# 16_-ETH_SWITCH.net
KiCad netlist of a schematic drawn in Altium Designer
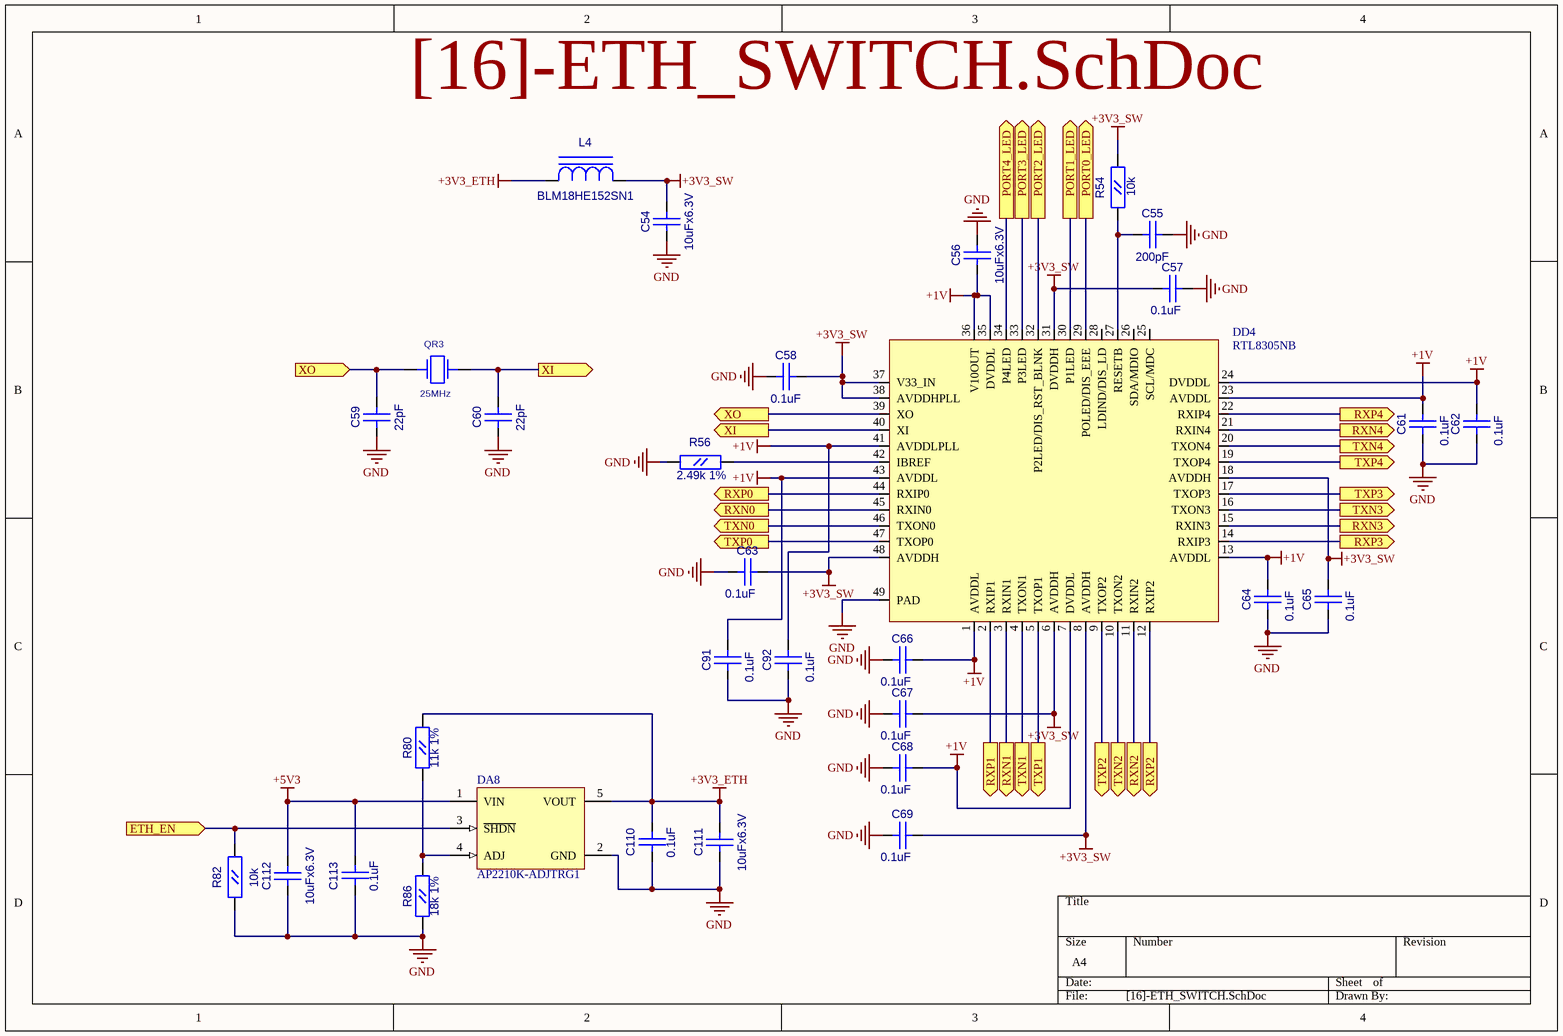
[diagram p0: [16]-ETH_SWITCH.SchDoc]

(export (version "E")
  (design (tool "Eeschema 10.0.6"))
  (components
    (comp (ref "C54")
      (value "10uFx6.3V")
      (footprint "CC0805")
      (description "CC0805")
      (libsource (lib "fizik_lib") (part "CC0805"))
    )
    (comp (ref "C55")
      (value "200pF")
      (footprint "CC0603")
      (description "CC0603")
      (libsource (lib "fizik_lib") (part "CC0603"))
    )
    (comp (ref "C56")
      (value "10uFx6.3V")
      (footprint "CC0805")
      (description "CC0805")
      (libsource (lib "fizik_lib") (part "CC0805"))
    )
    (comp (ref "C57")
      (value "0.1uF")
      (footprint "CC0603")
      (description "CC0603")
      (libsource (lib "fizik_lib") (part "CC0603"))
    )
    (comp (ref "C58")
      (value "0.1uF")
      (footprint "CC0603")
      (description "CC0603")
      (libsource (lib "fizik_lib") (part "CC0603"))
    )
    (comp (ref "C59")
      (value "22pF")
      (footprint "CC0603")
      (description "CC0603")
      (libsource (lib "fizik_lib") (part "CC0603"))
    )
    (comp (ref "C60")
      (value "22pF")
      (footprint "CC0603")
      (description "CC0603")
      (libsource (lib "fizik_lib") (part "CC0603"))
    )
    (comp (ref "C61")
      (value "0.1uF")
      (footprint "CC0603")
      (description "CC0603")
      (libsource (lib "fizik_lib") (part "CC0603"))
    )
    (comp (ref "C62")
      (value "0.1uF")
      (footprint "CC0603")
      (description "CC0603")
      (libsource (lib "fizik_lib") (part "CC0603"))
    )
    (comp (ref "C63")
      (value "0.1uF")
      (footprint "CC0603")
      (description "CC0603")
      (libsource (lib "fizik_lib") (part "CC0603"))
    )
    (comp (ref "C64")
      (value "0.1uF")
      (footprint "CC0603")
      (description "CC0603")
      (libsource (lib "fizik_lib") (part "CC0603"))
    )
    (comp (ref "C65")
      (value "0.1uF")
      (footprint "CC0603")
      (description "CC0603")
      (libsource (lib "fizik_lib") (part "CC0603"))
    )
    (comp (ref "C66")
      (value "0.1uF")
      (footprint "CC0603")
      (description "CC0603")
      (libsource (lib "fizik_lib") (part "CC0603"))
    )
    (comp (ref "C67")
      (value "0.1uF")
      (footprint "CC0603")
      (description "CC0603")
      (libsource (lib "fizik_lib") (part "CC0603"))
    )
    (comp (ref "C68")
      (value "0.1uF")
      (footprint "CC0603")
      (description "CC0603")
      (libsource (lib "fizik_lib") (part "CC0603"))
    )
    (comp (ref "C69")
      (value "0.1uF")
      (footprint "CC0603")
      (description "CC0603")
      (libsource (lib "fizik_lib") (part "CC0603"))
    )
    (comp (ref "C91")
      (value "0.1uF")
      (footprint "CC0603")
      (description "CC0603")
      (libsource (lib "fizik_lib") (part "CC0603"))
    )
    (comp (ref "C92")
      (value "0.1uF")
      (footprint "CC0603")
      (description "CC0603")
      (libsource (lib "fizik_lib") (part "CC0603"))
    )
    (comp (ref "C110")
      (value "0.1uF")
      (footprint "CC0603")
      (description "CC0603")
      (libsource (lib "gprs_modem_2") (part "CC0603"))
    )
    (comp (ref "C111")
      (value "10uFx6.3V")
      (footprint "CC0805")
      (description "CC0805")
      (libsource (lib "gprs_modem_2") (part "CC0805"))
    )
    (comp (ref "C112")
      (value "10uFx6.3V")
      (footprint "CC0805")
      (description "CC0805")
      (libsource (lib "gprs_modem_2") (part "CC0805"))
    )
    (comp (ref "C113")
      (value "0.1uF")
      (footprint "CC0603")
      (description "CC0603")
      (libsource (lib "gprs_modem_2") (part "CC0603"))
    )
    (comp (ref "DA8")
      (value "AP2210K-ADJTRG1")
      (footprint "SOT23-5")
      (fields (field (name "PUBLISHER") "Altium Limited"))
      (libsource (lib "gprs_modem_2") (part "MCP1824T-ADJE/OT"))
    )
    (comp (ref "DD4")
      (value "RTL8305NB")
      (footprint "QFN48_ISL")
      (libsource (lib "fizik_lib") (part "RTL8305NB"))
    )
    (comp (ref "L4")
      (value "BLM18HE152SN1")
      (footprint "L0603")
      (description "L0603")
      (libsource (lib "gprs_modem_2") (part "L0603"))
    )
    (comp (ref "QR3")
      (value "25MHz")
      (footprint "AC5032_2")
      (description "AC5032/2")
      (libsource (lib "fizik_lib") (part "AC5032_2"))
    )
    (comp (ref "R54")
      (value "10k")
      (footprint "RC0603")
      (description "RC0603")
      (libsource (lib "fizik_lib") (part "RC0603"))
    )
    (comp (ref "R56")
      (value "2.49k 1%")
      (footprint "RC0603")
      (description "RC0603")
      (libsource (lib "fizik_lib") (part "RC0603"))
    )
    (comp (ref "R80")
      (value "11k 1%")
      (footprint "RC0603")
      (description "RC0603")
      (libsource (lib "gprs_modem_2") (part "RC0603"))
    )
    (comp (ref "R82")
      (value "10k")
      (footprint "RC0603")
      (description "RC0603")
      (libsource (lib "gprs_modem_2") (part "RC0603"))
    )
    (comp (ref "R86")
      (value "18k 1%")
      (footprint "RC0603")
      (description "RC0603")
      (libsource (lib "gprs_modem_2") (part "RC0603"))
    )
  )
  (nets
    (net (code "1") (name "+1V") (class "Default")
      (node (ref "C56") (pin "1") (pinfunction "A_1") (pintype "passive"))
      (node (ref "C61") (pin "2") (pinfunction "B_2") (pintype "passive"))
      (node (ref "C62") (pin "2") (pinfunction "B_2") (pintype "passive"))
      (node (ref "C64") (pin "2") (pinfunction "B_2") (pintype "passive"))
      (node (ref "C66") (pin "2") (pinfunction "B_2") (pintype "passive"))
      (node (ref "C68") (pin "2") (pinfunction "B_2") (pintype "passive"))
      (node (ref "C91") (pin "2") (pinfunction "B_2") (pintype "passive"))
      (node (ref "C92") (pin "2") (pinfunction "B_2") (pintype "passive"))
      (node (ref "DD4") (pin "1") (pinfunction "AVDDL_1") (pintype "passive"))
      (node (ref "DD4") (pin "13") (pinfunction "AVDDL_13") (pintype "passive"))
      (node (ref "DD4") (pin "23") (pinfunction "AVDDL_23") (pintype "passive"))
      (node (ref "DD4") (pin "24") (pinfunction "DVDDL_24") (pintype "passive"))
      (node (ref "DD4") (pin "35") (pinfunction "DVDDL_35") (pintype "passive"))
      (node (ref "DD4") (pin "36") (pinfunction "V10OUT_36") (pintype "passive"))
      (node (ref "DD4") (pin "41") (pinfunction "AVDDLPLL_41") (pintype "passive"))
      (node (ref "DD4") (pin "43") (pinfunction "AVDDL_43") (pintype "passive"))
      (node (ref "DD4") (pin "7") (pinfunction "DVDDL_7") (pintype "passive"))
    )
    (net (code "2") (name "+3V3_ETH") (class "Default")
      (node (ref "C110") (pin "1") (pinfunction "A_1") (pintype "passive"))
      (node (ref "C111") (pin "2") (pinfunction "B_2") (pintype "passive"))
      (node (ref "DA8") (pin "5") (pinfunction "VOUT_5") (pintype "power_in"))
      (node (ref "L4") (pin "1") (pinfunction "A_1") (pintype "passive"))
      (node (ref "R80") (pin "2") (pinfunction "B_2") (pintype "passive"))
    )
    (net (code "3") (name "+3V3_SW") (class "Default")
      (node (ref "C54") (pin "2") (pinfunction "B_2") (pintype "passive"))
      (node (ref "C57") (pin "1") (pinfunction "A_1") (pintype "passive"))
      (node (ref "C58") (pin "2") (pinfunction "B_2") (pintype "passive"))
      (node (ref "C63") (pin "2") (pinfunction "B_2") (pintype "passive"))
      (node (ref "C65") (pin "2") (pinfunction "B_2") (pintype "passive"))
      (node (ref "C67") (pin "2") (pinfunction "B_2") (pintype "passive"))
      (node (ref "C69") (pin "2") (pinfunction "B_2") (pintype "passive"))
      (node (ref "DD4") (pin "18") (pinfunction "AVDDH_18") (pintype "passive"))
      (node (ref "DD4") (pin "31") (pinfunction "DVDDH_31") (pintype "passive"))
      (node (ref "DD4") (pin "37") (pinfunction "V33_IN_37") (pintype "passive"))
      (node (ref "DD4") (pin "38") (pinfunction "AVDDHPLL_38") (pintype "passive"))
      (node (ref "DD4") (pin "48") (pinfunction "AVDDH_48") (pintype "passive"))
      (node (ref "DD4") (pin "6") (pinfunction "AVDDH_6") (pintype "passive"))
      (node (ref "DD4") (pin "8") (pinfunction "AVDDH_8") (pintype "passive"))
      (node (ref "L4") (pin "2") (pinfunction "C_2") (pintype "passive"))
      (node (ref "R54") (pin "2") (pinfunction "B_2") (pintype "passive"))
    )
    (net (code "4") (name "+5V3") (class "Default")
      (node (ref "C112") (pin "2") (pinfunction "B_2") (pintype "passive"))
      (node (ref "C113") (pin "1") (pinfunction "A_1") (pintype "passive"))
      (node (ref "DA8") (pin "1") (pinfunction "VIN_1") (pintype "power_in"))
    )
    (net (code "5") (name "/ETH_EN") (class "Default")
      (node (ref "DA8") (pin "3") (pinfunction "~{SHDN}_3") (pintype "input"))
      (node (ref "R82") (pin "2") (pinfunction "B_2") (pintype "passive"))
    )
    (net (code "6") (name "/PORT0_LED") (class "Default")
      (node (ref "DD4") (pin "29") (pinfunction "POLED/DIS_EEE_29") (pintype "passive"))
    )
    (net (code "7") (name "/PORT1_LED") (class "Default")
      (node (ref "DD4") (pin "30") (pinfunction "P1LED_30") (pintype "passive"))
    )
    (net (code "8") (name "/PORT2_LED") (class "Default")
      (node (ref "DD4") (pin "32") (pinfunction "P2LED/DIS_RST_BLNK_32") (pintype "passive"))
    )
    (net (code "9") (name "/PORT3_LED") (class "Default")
      (node (ref "DD4") (pin "33") (pinfunction "P3LED_33") (pintype "passive"))
    )
    (net (code "10") (name "/PORT4_LED") (class "Default")
      (node (ref "DD4") (pin "34") (pinfunction "P4LED_34") (pintype "passive"))
    )
    (net (code "11") (name "/RXN0") (class "Default")
      (node (ref "DD4") (pin "45") (pinfunction "RXIN0_45") (pintype "passive"))
    )
    (net (code "12") (name "/RXN1") (class "Default")
      (node (ref "DD4") (pin "3") (pinfunction "RXIN1_3") (pintype "passive"))
    )
    (net (code "13") (name "/RXN2") (class "Default")
      (node (ref "DD4") (pin "11") (pinfunction "RXIN2_11") (pintype "passive"))
    )
    (net (code "14") (name "/RXN3") (class "Default")
      (node (ref "DD4") (pin "15") (pinfunction "RXIN3_15") (pintype "passive"))
    )
    (net (code "15") (name "/RXN4") (class "Default")
      (node (ref "DD4") (pin "21") (pinfunction "RXIN4_21") (pintype "passive"))
    )
    (net (code "16") (name "/RXP0") (class "Default")
      (node (ref "DD4") (pin "44") (pinfunction "RXIP0_44") (pintype "passive"))
    )
    (net (code "17") (name "/RXP1") (class "Default")
      (node (ref "DD4") (pin "2") (pinfunction "RXIP1_2") (pintype "passive"))
    )
    (net (code "18") (name "/RXP2") (class "Default")
      (node (ref "DD4") (pin "12") (pinfunction "RXIP2_12") (pintype "passive"))
    )
    (net (code "19") (name "/RXP3") (class "Default")
      (node (ref "DD4") (pin "14") (pinfunction "RXIP3_14") (pintype "passive"))
    )
    (net (code "20") (name "/RXP4") (class "Default")
      (node (ref "DD4") (pin "22") (pinfunction "RXIP4_22") (pintype "passive"))
    )
    (net (code "21") (name "/TXN0") (class "Default")
      (node (ref "DD4") (pin "46") (pinfunction "TXON0_46") (pintype "passive"))
    )
    (net (code "22") (name "/TXN1") (class "Default")
      (node (ref "DD4") (pin "4") (pinfunction "TXON1_4") (pintype "passive"))
    )
    (net (code "23") (name "/TXN2") (class "Default")
      (node (ref "DD4") (pin "10") (pinfunction "TXON2_10") (pintype "passive"))
    )
    (net (code "24") (name "/TXN3") (class "Default")
      (node (ref "DD4") (pin "16") (pinfunction "TXON3_16") (pintype "passive"))
    )
    (net (code "25") (name "/TXN4") (class "Default")
      (node (ref "DD4") (pin "20") (pinfunction "TXON4_20") (pintype "passive"))
    )
    (net (code "26") (name "/TXP0") (class "Default")
      (node (ref "DD4") (pin "47") (pinfunction "TXOP0_47") (pintype "passive"))
    )
    (net (code "27") (name "/TXP1") (class "Default")
      (node (ref "DD4") (pin "5") (pinfunction "TXOP1_5") (pintype "passive"))
    )
    (net (code "28") (name "/TXP2") (class "Default")
      (node (ref "DD4") (pin "9") (pinfunction "TXOP2_9") (pintype "passive"))
    )
    (net (code "29") (name "/TXP3") (class "Default")
      (node (ref "DD4") (pin "17") (pinfunction "TXOP3_17") (pintype "passive"))
    )
    (net (code "30") (name "/TXP4") (class "Default")
      (node (ref "DD4") (pin "19") (pinfunction "TXOP4_19") (pintype "passive"))
    )
    (net (code "31") (name "/XI") (class "Default")
      (node (ref "C60") (pin "2") (pinfunction "B_2") (pintype "passive"))
      (node (ref "DD4") (pin "40") (pinfunction "XI_40") (pintype "passive"))
      (node (ref "QR3") (pin "2") (pintype "passive"))
    )
    (net (code "32") (name "/XO") (class "Default")
      (node (ref "C59") (pin "2") (pinfunction "B_2") (pintype "passive"))
      (node (ref "DD4") (pin "39") (pinfunction "XO_39") (pintype "passive"))
      (node (ref "QR3") (pin "1") (pintype "passive"))
    )
    (net (code "33") (name "GND") (class "Default")
      (node (ref "C110") (pin "2") (pinfunction "B_2") (pintype "passive"))
      (node (ref "C111") (pin "1") (pinfunction "A_1") (pintype "passive"))
      (node (ref "C112") (pin "1") (pinfunction "A_1") (pintype "passive"))
      (node (ref "C113") (pin "2") (pinfunction "B_2") (pintype "passive"))
      (node (ref "C54") (pin "1") (pinfunction "A_1") (pintype "passive"))
      (node (ref "C55") (pin "2") (pinfunction "B_2") (pintype "passive"))
      (node (ref "C56") (pin "2") (pinfunction "B_2") (pintype "passive"))
      (node (ref "C57") (pin "2") (pinfunction "B_2") (pintype "passive"))
      (node (ref "C58") (pin "1") (pinfunction "A_1") (pintype "passive"))
      (node (ref "C59") (pin "1") (pinfunction "A_1") (pintype "passive"))
      (node (ref "C60") (pin "1") (pinfunction "A_1") (pintype "passive"))
      (node (ref "C61") (pin "1") (pinfunction "A_1") (pintype "passive"))
      (node (ref "C62") (pin "1") (pinfunction "A_1") (pintype "passive"))
      (node (ref "C63") (pin "1") (pinfunction "A_1") (pintype "passive"))
      (node (ref "C64") (pin "1") (pinfunction "A_1") (pintype "passive"))
      (node (ref "C65") (pin "1") (pinfunction "A_1") (pintype "passive"))
      (node (ref "C66") (pin "1") (pinfunction "A_1") (pintype "passive"))
      (node (ref "C67") (pin "1") (pinfunction "A_1") (pintype "passive"))
      (node (ref "C68") (pin "1") (pinfunction "A_1") (pintype "passive"))
      (node (ref "C69") (pin "1") (pinfunction "A_1") (pintype "passive"))
      (node (ref "C91") (pin "1") (pinfunction "A_1") (pintype "passive"))
      (node (ref "C92") (pin "1") (pinfunction "A_1") (pintype "passive"))
      (node (ref "DA8") (pin "2") (pinfunction "GND_2") (pintype "power_in"))
      (node (ref "DD4") (pin "49") (pinfunction "PAD_49") (pintype "passive"))
      (node (ref "R56") (pin "1") (pinfunction "A_1") (pintype "passive"))
      (node (ref "R82") (pin "1") (pinfunction "A_1") (pintype "passive"))
      (node (ref "R86") (pin "1") (pinfunction "A_1") (pintype "passive"))
    )
    (net (code "34") (name "Net-(C55-A)") (class "Default")
      (node (ref "C55") (pin "1") (pinfunction "A_1") (pintype "passive"))
      (node (ref "DD4") (pin "27") (pinfunction "RESETB_27") (pintype "passive"))
      (node (ref "R54") (pin "1") (pinfunction "A_1") (pintype "passive"))
    )
    (net (code "35") (name "Net-(DA8-ADJ)") (class "Default")
      (node (ref "DA8") (pin "4") (pinfunction "ADJ_4") (pintype "input"))
      (node (ref "R80") (pin "1") (pinfunction "A_1") (pintype "passive"))
      (node (ref "R86") (pin "2") (pinfunction "B_2") (pintype "passive"))
    )
    (net (code "36") (name "Net-(DD4-IBREF)") (class "Default")
      (node (ref "DD4") (pin "42") (pinfunction "IBREF_42") (pintype "passive"))
      (node (ref "R56") (pin "2") (pinfunction "B_2") (pintype "passive"))
    )
    (net (code "37") (name "unconnected-(DD4-LDIND{slash}DIS_LD-Pad28)") (class "Default")
      (node (ref "DD4") (pin "28") (pinfunction "LDIND/DIS_LD_28") (pintype "passive"))
    )
    (net (code "38") (name "unconnected-(DD4-SCL{slash}MDC-Pad25)") (class "Default")
      (node (ref "DD4") (pin "25") (pinfunction "SCL/MDC_25") (pintype "passive"))
    )
    (net (code "39") (name "unconnected-(DD4-SDA{slash}MDIO-Pad26)") (class "Default")
      (node (ref "DD4") (pin "26") (pinfunction "SDA/MDIO_26") (pintype "passive"))
    )
  )
)
